# Etherent.net
KiCad netlist of a schematic drawn in Altium Designer
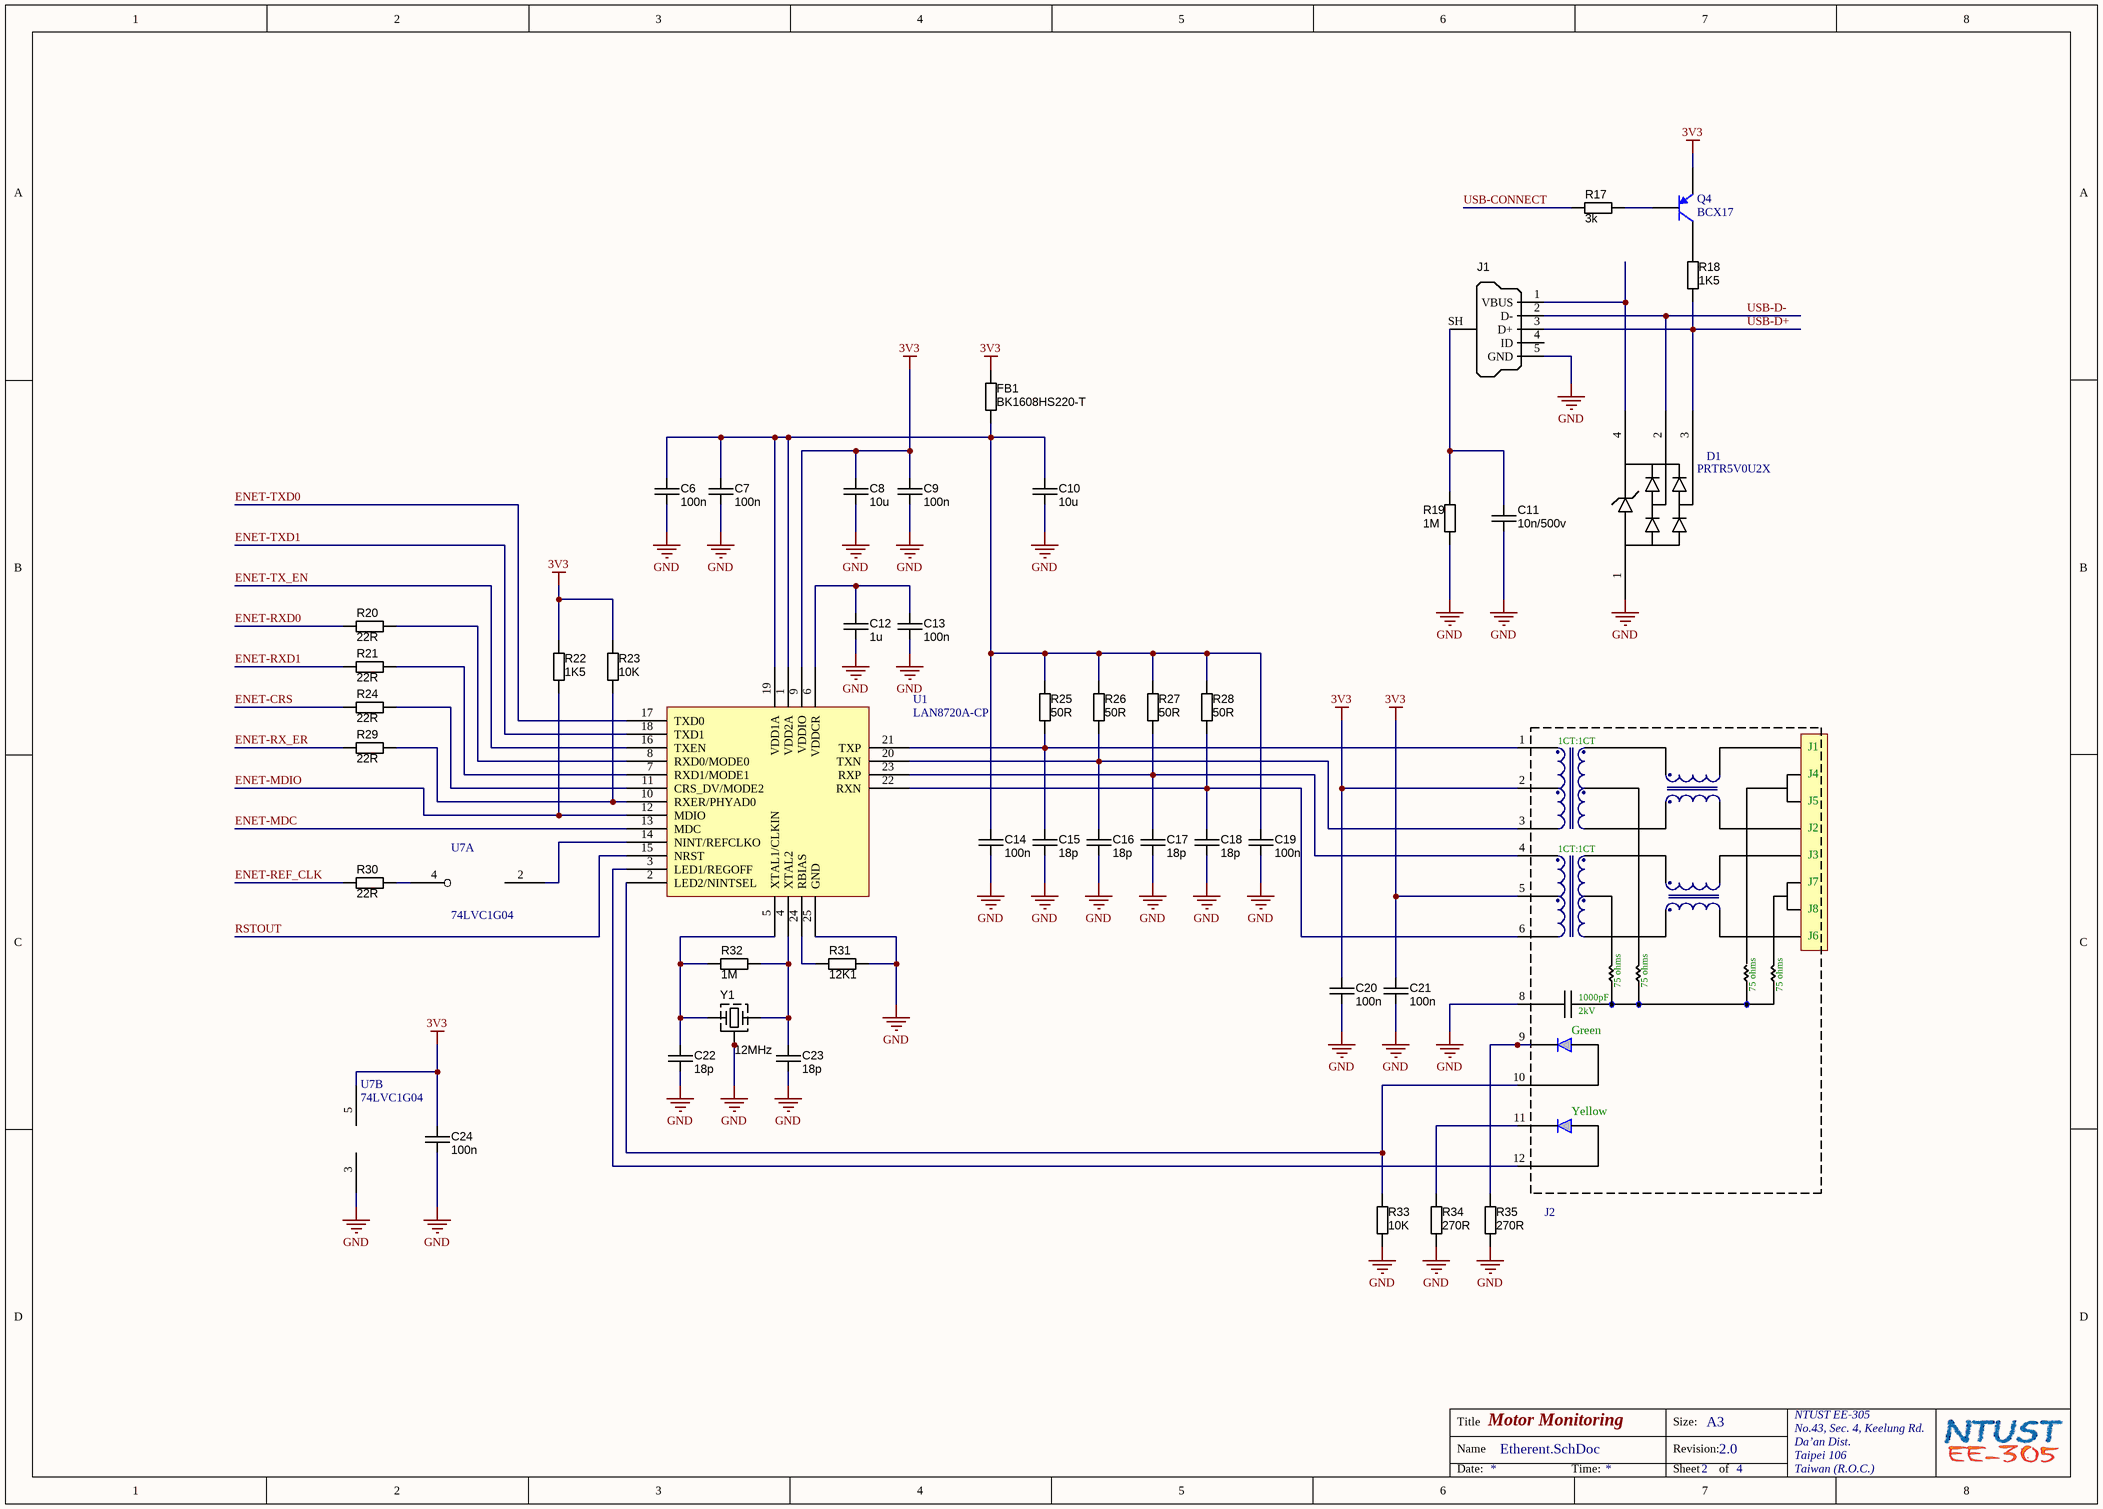
[diagram p0: Etherent.SchDoc]

(export (version "E")
  (design (tool "Eeschema 10.0.6"))
  (components
    (comp (ref "C6")
      (value "100n")
      (footprint "CAPC1608N")
      (description "Capacitor SMD Cer 100nF 10% 50V X7R 0805")
      (fields (field (name "TOLERANCE") "?0%") (field (name "Comment") "approved sub OK"))
      (libsource (lib "PBL - Capacitors") (part "CAPC_100n_0805"))
    )
    (comp (ref "C7")
      (value "100n")
      (footprint "CAPC1608N")
      (description "Capacitor SMD Cer 100nF 10% 50V X7R 0805")
      (fields (field (name "TOLERANCE") "?0%") (field (name "Comment") "approved sub OK"))
      (libsource (lib "PBL - Capacitors") (part "CAPC_100n_0805"))
    )
    (comp (ref "C8")
      (value "10u")
      (footprint "CAPC1608N")
      (description "Capacitor SMD Cer 100nF 10% 50V X7R 0805")
      (fields (field (name "TOLERANCE") "?0%") (field (name "Comment") "approved sub OK"))
      (libsource (lib "PBL - Capacitors") (part "CAPC_100n_0805"))
    )
    (comp (ref "C9")
      (value "100n")
      (footprint "CAPC1608N")
      (description "Capacitor SMD Cer 100nF 10% 50V X7R 0805")
      (fields (field (name "TOLERANCE") "?0%") (field (name "Comment") "approved sub OK"))
      (libsource (lib "PBL - Capacitors") (part "CAPC_100n_0805"))
    )
    (comp (ref "C10")
      (value "10u")
      (footprint "CAPC3216N")
      (description "Capacitor SMD Cer 100nF 10% 50V X7R 0805")
      (fields (field (name "TOLERANCE") "?0%") (field (name "Comment") "approved sub OK"))
      (libsource (lib "PBL - Capacitors") (part "CAPC_100n_0805"))
    )
    (comp (ref "C11")
      (value "10n/500v")
      (footprint "CAPC1608N")
      (description "Capacitor SMD Cer 100nF 10% 50V X7R 0805")
      (fields (field (name "TOLERANCE") "?0%") (field (name "Comment") "approved sub OK"))
      (libsource (lib "PBL - Capacitors") (part "CAPC_100n_0805"))
    )
    (comp (ref "C12")
      (value "1u")
      (footprint "CAPC2012N")
      (description "Capacitor SMD Cer 100nF 10% 50V X7R 0805")
      (fields (field (name "TOLERANCE") "?0%") (field (name "Comment") "approved sub OK"))
      (libsource (lib "PBL - Capacitors") (part "CAPC_100n_0805"))
    )
    (comp (ref "C13")
      (value "100n")
      (footprint "CAPC1608N")
      (description "Capacitor SMD Cer 100nF 10% 50V X7R 0805")
      (fields (field (name "TOLERANCE") "?0%") (field (name "Comment") "approved sub OK"))
      (libsource (lib "PBL - Capacitors") (part "CAPC_100n_0805"))
    )
    (comp (ref "C14")
      (value "100n")
      (footprint "CAPC1608N")
      (description "Capacitor SMD Cer 100nF 10% 50V X7R 0805")
      (fields (field (name "TOLERANCE") "?0%") (field (name "Comment") "approved sub OK"))
      (libsource (lib "PBL - Capacitors") (part "CAPC_100n_0805"))
    )
    (comp (ref "C15")
      (value "18p")
      (footprint "CAPC1005N")
      (description "Capacitor SMD Cer 100nF 10% 50V X7R 0805")
      (fields (field (name "TOLERANCE") "?0%") (field (name "Comment") "approved sub OK"))
      (libsource (lib "PBL - Capacitors") (part "CAPC_100n_0805"))
    )
    (comp (ref "C16")
      (value "18p")
      (footprint "CAPC1005N")
      (description "Capacitor SMD Cer 100nF 10% 50V X7R 0805")
      (fields (field (name "TOLERANCE") "?0%") (field (name "Comment") "approved sub OK"))
      (libsource (lib "PBL - Capacitors") (part "CAPC_100n_0805"))
    )
    (comp (ref "C17")
      (value "18p")
      (footprint "CAPC1005N")
      (description "Capacitor SMD Cer 100nF 10% 50V X7R 0805")
      (fields (field (name "TOLERANCE") "?0%") (field (name "Comment") "approved sub OK"))
      (libsource (lib "PBL - Capacitors") (part "CAPC_100n_0805"))
    )
    (comp (ref "C18")
      (value "18p")
      (footprint "CAPC1005N")
      (description "Capacitor SMD Cer 100nF 10% 50V X7R 0805")
      (fields (field (name "TOLERANCE") "?0%") (field (name "Comment") "approved sub OK"))
      (libsource (lib "PBL - Capacitors") (part "CAPC_100n_0805"))
    )
    (comp (ref "C19")
      (value "100n")
      (footprint "CAPC1608N")
      (description "Capacitor SMD Cer 100nF 10% 50V X7R 0805")
      (fields (field (name "TOLERANCE") "?0%") (field (name "Comment") "approved sub OK"))
      (libsource (lib "PBL - Capacitors") (part "CAPC_100n_0805"))
    )
    (comp (ref "C20")
      (value "100n")
      (footprint "CAPC1608N")
      (description "Capacitor SMD Cer 100nF 10% 50V X7R 0805")
      (fields (field (name "TOLERANCE") "?0%") (field (name "Comment") "approved sub OK"))
      (libsource (lib "PBL - Capacitors") (part "CAPC_100n_0805"))
    )
    (comp (ref "C21")
      (value "100n")
      (footprint "CAPC1608N")
      (description "Capacitor SMD Cer 100nF 10% 50V X7R 0805")
      (fields (field (name "TOLERANCE") "?0%") (field (name "Comment") "approved sub OK"))
      (libsource (lib "PBL - Capacitors") (part "CAPC_100n_0805"))
    )
    (comp (ref "C22")
      (value "18p")
      (footprint "CAPC1005N")
      (description "Capacitor SMD Cer 100nF 10% 50V X7R 0805")
      (fields (field (name "TOLERANCE") "?0%") (field (name "Comment") "approved sub OK"))
      (libsource (lib "PBL - Capacitors") (part "CAPC_100n_0805"))
    )
    (comp (ref "C23")
      (value "18p")
      (footprint "CAPC1005N")
      (description "Capacitor SMD Cer 100nF 10% 50V X7R 0805")
      (fields (field (name "TOLERANCE") "?0%") (field (name "Comment") "approved sub OK"))
      (libsource (lib "PBL - Capacitors") (part "CAPC_100n_0805"))
    )
    (comp (ref "C24")
      (value "100n")
      (footprint "CAPC1608N")
      (description "Capacitor SMD Cer 100nF 10% 50V X7R 0805")
      (fields (field (name "TOLERANCE") "?0%") (field (name "Comment") "approved sub OK"))
      (libsource (lib "PBL - Capacitors") (part "CAPC_100n_0805"))
    )
    (comp (ref "D1")
      (value "PRTR5V0U2X")
      (footprint "SOT190P230X120-4N")
      (libsource (lib "Schlib1") (part "PRTR5V0U2X"))
    )
    (comp (ref "FB1")
      (value "BK1608HS220-T")
      (footprint "CAPC3216N")
      (description "Resistor SMD chip 330 Ohm 0.063W 5% 0402")
      (fields (field (name "TOLERANCE") "?%") (field (name "Comment") "Thick Film"))
      (libsource (lib "") (part "RES_330R_0402_5%_1"))
    )
    (comp (ref "J1")
      (value "USB Micro Type B")
      (footprint "USB_Micro-B_FCI_SMD")
      (description "Connector SMD-THD USB Micro Type B middle mount")
      (libsource (lib "PBL - Connectors") (part "USB_Micro_TypeB_FCI"))
    )
    (comp (ref "J2")
      (value "~")
      (footprint "ARJC01-111002T")
      (description "10/100 Base-Tx Tap Up RJ45 with LED")
      (libsource (lib "Schlib1") (part "ARJC01-111002T"))
    )
    (comp (ref "Q4")
      (value "BCX17")
      (footprint "SOT23-3N")
      (description "PNP General Purpose Transistors")
      (fields (field (name "PUBLISHER") "Altium Limited"))
      (libsource (lib "Schlib1") (part "BCX17"))
    )
    (comp (ref "R17")
      (value "3k")
      (footprint "RESC1005N")
      (description "Resistor SMD chip 330 Ohm 0.063W 5% 0402")
      (fields (field (name "TOLERANCE") "?%") (field (name "Comment") "Thick Film"))
      (libsource (lib "") (part "RES_330R_0402_5%_2"))
    )
    (comp (ref "R18")
      (value "1K5")
      (footprint "RESC1005N")
      (description "Resistor SMD chip 330 Ohm 0.063W 5% 0402")
      (fields (field (name "TOLERANCE") "?%") (field (name "Comment") "Thick Film"))
      (libsource (lib "PBL - Resistors") (part "RES_330R_0402_5%"))
    )
    (comp (ref "R19")
      (value "1M")
      (footprint "RESC1005N")
      (description "Resistor SMD chip 330 Ohm 0.063W 5% 0402")
      (fields (field (name "TOLERANCE") "?%") (field (name "Comment") "Thick Film"))
      (libsource (lib "") (part "RES_330R_0402_5%_1"))
    )
    (comp (ref "R20")
      (value "22R")
      (footprint "RESC1005N")
      (description "Resistor SMD chip 330 Ohm 0.063W 5% 0402")
      (fields (field (name "TOLERANCE") "?%") (field (name "Comment") "Thick Film"))
      (libsource (lib "") (part "RES_330R_0402_5%_3"))
    )
    (comp (ref "R21")
      (value "22R")
      (footprint "RESC1005N")
      (description "Resistor SMD chip 330 Ohm 0.063W 5% 0402")
      (fields (field (name "TOLERANCE") "?%") (field (name "Comment") "Thick Film"))
      (libsource (lib "") (part "RES_330R_0402_5%_3"))
    )
    (comp (ref "R22")
      (value "1K5")
      (footprint "RESC1005N")
      (description "Resistor SMD chip 330 Ohm 0.063W 5% 0402")
      (fields (field (name "TOLERANCE") "?%") (field (name "Comment") "Thick Film"))
      (libsource (lib "PBL - Resistors") (part "RES_330R_0402_5%"))
    )
    (comp (ref "R23")
      (value "10K")
      (footprint "RESC1005N")
      (description "Resistor SMD chip 330 Ohm 0.063W 5% 0402")
      (fields (field (name "TOLERANCE") "?%") (field (name "Comment") "Thick Film"))
      (libsource (lib "PBL - Resistors") (part "RES_330R_0402_5%"))
    )
    (comp (ref "R24")
      (value "22R")
      (footprint "RESC1005N")
      (description "Resistor SMD chip 330 Ohm 0.063W 5% 0402")
      (fields (field (name "TOLERANCE") "?%") (field (name "Comment") "Thick Film"))
      (libsource (lib "") (part "RES_330R_0402_5%_3"))
    )
    (comp (ref "R25")
      (value "50R")
      (footprint "RESC1005N")
      (description "Resistor SMD chip 330 Ohm 0.063W 5% 0402")
      (fields (field (name "TOLERANCE") "?%") (field (name "Comment") "Thick Film"))
      (libsource (lib "PBL - Resistors") (part "RES_330R_0402_5%"))
    )
    (comp (ref "R26")
      (value "50R")
      (footprint "RESC1005N")
      (description "Resistor SMD chip 330 Ohm 0.063W 5% 0402")
      (fields (field (name "TOLERANCE") "?%") (field (name "Comment") "Thick Film"))
      (libsource (lib "PBL - Resistors") (part "RES_330R_0402_5%"))
    )
    (comp (ref "R27")
      (value "50R")
      (footprint "RESC1005N")
      (description "Resistor SMD chip 330 Ohm 0.063W 5% 0402")
      (fields (field (name "TOLERANCE") "?%") (field (name "Comment") "Thick Film"))
      (libsource (lib "PBL - Resistors") (part "RES_330R_0402_5%"))
    )
    (comp (ref "R28")
      (value "50R")
      (footprint "RESC1005N")
      (description "Resistor SMD chip 330 Ohm 0.063W 5% 0402")
      (fields (field (name "TOLERANCE") "?%") (field (name "Comment") "Thick Film"))
      (libsource (lib "PBL - Resistors") (part "RES_330R_0402_5%"))
    )
    (comp (ref "R29")
      (value "22R")
      (footprint "RESC1005N")
      (description "Resistor SMD chip 330 Ohm 0.063W 5% 0402")
      (fields (field (name "TOLERANCE") "?%") (field (name "Comment") "Thick Film"))
      (libsource (lib "") (part "RES_330R_0402_5%_2"))
    )
    (comp (ref "R30")
      (value "22R")
      (footprint "RESC1005N")
      (description "Resistor SMD chip 330 Ohm 0.063W 5% 0402")
      (fields (field (name "TOLERANCE") "?%") (field (name "Comment") "Thick Film"))
      (libsource (lib "") (part "RES_330R_0402_5%_3"))
    )
    (comp (ref "R31")
      (value "12K1")
      (footprint "RESC1005N")
      (description "Resistor SMD chip 330 Ohm 0.063W 5% 0402")
      (fields (field (name "TOLERANCE") "?%") (field (name "Comment") "Thick Film"))
      (libsource (lib "") (part "RES_330R_0402_5%_2"))
    )
    (comp (ref "R32")
      (value "1M")
      (footprint "RESC1005N")
      (description "Resistor SMD chip 330 Ohm 0.063W 5% 0402")
      (fields (field (name "TOLERANCE") "?%") (field (name "Comment") "Thick Film"))
      (libsource (lib "") (part "RES_330R_0402_5%_3"))
    )
    (comp (ref "R33")
      (value "10K")
      (footprint "RESC1005N")
      (description "Resistor SMD chip 330 Ohm 0.063W 5% 0402")
      (fields (field (name "TOLERANCE") "?%") (field (name "Comment") "Thick Film"))
      (libsource (lib "PBL - Resistors") (part "RES_330R_0402_5%"))
    )
    (comp (ref "R34")
      (value "270R")
      (footprint "RESC1005N")
      (description "Resistor SMD chip 330 Ohm 0.063W 5% 0402")
      (fields (field (name "TOLERANCE") "?%") (field (name "Comment") "Thick Film"))
      (libsource (lib "") (part "RES_330R_0402_5%_1"))
    )
    (comp (ref "R35")
      (value "270R")
      (footprint "RESC1005N")
      (description "Resistor SMD chip 330 Ohm 0.063W 5% 0402")
      (fields (field (name "TOLERANCE") "?%") (field (name "Comment") "Thick Film"))
      (libsource (lib "") (part "RES_330R_0402_5%_1"))
    )
    (comp (ref "U1")
      (value "LAN8720A-CP")
      (footprint "QFN-MJ24")
      (libsource (lib "Schlib1") (part "LAN8720A-CP"))
    )
    (comp (ref "U7")
      (value "74LVC1G04")
      (footprint "SOT-23-CT5_N")
      (libsource (lib "Schlib1") (part "74LVC1G04"))
    )
    (comp (ref "Y1")
      (value "12MHz")
      (footprint "CRYSTAL_4-LCC")
      (description "Oscillator Crystal 27.12 MHz 10ppm")
      (libsource (lib "PBL - Resonators") (part "CRYSTAL_27M12"))
    )
  )
  (nets
    (net (code "1") (name "/ENET-CRS") (class "Default")
      (node (ref "R24") (pin "1") (pinfunction "1_1") (pintype "passive"))
    )
    (net (code "2") (name "/ENET-MDC") (class "Default")
      (node (ref "U1") (pin "13") (pinfunction "MDC_13") (pintype "passive"))
    )
    (net (code "3") (name "/ENET-MDIO") (class "Default")
      (node (ref "R22") (pin "2") (pinfunction "2_2") (pintype "passive"))
      (node (ref "U1") (pin "12") (pinfunction "MDIO_12") (pintype "passive"))
    )
    (net (code "4") (name "/ENET-REF_CLK") (class "Default")
      (node (ref "R30") (pin "1") (pinfunction "1_1") (pintype "passive"))
    )
    (net (code "5") (name "/ENET-RXD0") (class "Default")
      (node (ref "R20") (pin "1") (pinfunction "1_1") (pintype "passive"))
    )
    (net (code "6") (name "/ENET-RXD1") (class "Default")
      (node (ref "R21") (pin "1") (pinfunction "1_1") (pintype "passive"))
    )
    (net (code "7") (name "/ENET-RX_ER") (class "Default")
      (node (ref "R29") (pin "2") (pinfunction "2_2") (pintype "passive"))
    )
    (net (code "8") (name "/ENET-TXD0") (class "Default")
      (node (ref "U1") (pin "17") (pinfunction "TXD0_17") (pintype "passive"))
    )
    (net (code "9") (name "/ENET-TXD1") (class "Default")
      (node (ref "U1") (pin "18") (pinfunction "TXD1_18") (pintype "passive"))
    )
    (net (code "10") (name "/ENET-TX_EN") (class "Default")
      (node (ref "U1") (pin "16") (pinfunction "TXEN_16") (pintype "passive"))
    )
    (net (code "11") (name "/RSTOUT") (class "Default")
      (node (ref "U1") (pin "15") (pinfunction "NRST_15") (pintype "passive"))
    )
    (net (code "12") (name "/USB-CONNECT") (class "Default")
      (node (ref "R17") (pin "2") (pinfunction "2_2") (pintype "passive"))
    )
    (net (code "13") (name "/USB-D+") (class "Default")
      (node (ref "D1") (pin "3") (pinfunction "I/O_2_3") (pintype "passive"))
      (node (ref "J1") (pin "3") (pinfunction "D+_3") (pintype "passive"))
      (node (ref "R18") (pin "2") (pinfunction "2_2") (pintype "passive"))
    )
    (net (code "14") (name "/USB-D-") (class "Default")
      (node (ref "D1") (pin "2") (pinfunction "I/O_1_2") (pintype "passive"))
      (node (ref "J1") (pin "2") (pinfunction "D-_2") (pintype "passive"))
    )
    (net (code "15") (name "3V3") (class "Default")
      (node (ref "C20") (pin "1") (pintype "passive"))
      (node (ref "C21") (pin "1") (pintype "passive"))
      (node (ref "C24") (pin "1") (pintype "passive"))
      (node (ref "C8") (pin "1") (pintype "passive"))
      (node (ref "C9") (pin "1") (pintype "passive"))
      (node (ref "FB1") (pin "2") (pinfunction "2_2") (pintype "passive"))
      (node (ref "J2") (pin "2") (pinfunction "CTD_2") (pintype "passive"))
      (node (ref "J2") (pin "5") (pinfunction "CRD_5") (pintype "passive"))
      (node (ref "Q4") (pin "2") (pinfunction "E_2") (pintype "passive"))
      (node (ref "R22") (pin "1") (pinfunction "1_1") (pintype "passive"))
      (node (ref "R23") (pin "1") (pinfunction "1_1") (pintype "passive"))
      (node (ref "U1") (pin "9") (pinfunction "VDDIO_9") (pintype "passive"))
      (node (ref "U7") (pin "5") (pinfunction "VCC_5") (pintype "passive"))
    )
    (net (code "16") (name "GND") (class "Default")
      (node (ref "C10") (pin "2") (pintype "passive"))
      (node (ref "C11") (pin "2") (pintype "passive"))
      (node (ref "C12") (pin "2") (pintype "passive"))
      (node (ref "C13") (pin "2") (pintype "passive"))
      (node (ref "C14") (pin "1") (pintype "passive"))
      (node (ref "C15") (pin "1") (pintype "passive"))
      (node (ref "C16") (pin "1") (pintype "passive"))
      (node (ref "C17") (pin "1") (pintype "passive"))
      (node (ref "C18") (pin "1") (pintype "passive"))
      (node (ref "C19") (pin "1") (pintype "passive"))
      (node (ref "C20") (pin "2") (pintype "passive"))
      (node (ref "C21") (pin "2") (pintype "passive"))
      (node (ref "C22") (pin "1") (pintype "passive"))
      (node (ref "C23") (pin "1") (pintype "passive"))
      (node (ref "C24") (pin "2") (pintype "passive"))
      (node (ref "C6") (pin "2") (pintype "passive"))
      (node (ref "C7") (pin "2") (pintype "passive"))
      (node (ref "C8") (pin "2") (pintype "passive"))
      (node (ref "C9") (pin "2") (pintype "passive"))
      (node (ref "D1") (pin "1") (pinfunction "GND_1") (pintype "passive"))
      (node (ref "J1") (pin "5") (pinfunction "GND_5") (pintype "passive"))
      (node (ref "J2") (pin "8") (pinfunction "Shield_8") (pintype "passive"))
      (node (ref "R19") (pin "1") (pinfunction "1_1") (pintype "passive"))
      (node (ref "R31") (pin "1") (pinfunction "1_1") (pintype "passive"))
      (node (ref "R33") (pin "2") (pinfunction "2_2") (pintype "passive"))
      (node (ref "R34") (pin "1") (pinfunction "1_1") (pintype "passive"))
      (node (ref "R35") (pin "1") (pinfunction "1_1") (pintype "passive"))
      (node (ref "U1") (pin "25") (pinfunction "GND_25") (pintype "passive"))
      (node (ref "U7") (pin "3") (pinfunction "GND_3") (pintype "passive"))
      (node (ref "Y1") (pin "2") (pinfunction "GND_2") (pintype "passive"))
      (node (ref "Y1") (pin "4") (pinfunction "GND_4") (pintype "passive"))
    )
    (net (code "17") (name "Net-(D1-VCC)") (class "Default")
      (node (ref "D1") (pin "4") (pinfunction "VCC_4") (pintype "passive"))
      (node (ref "J1") (pin "1") (pinfunction "VBUS_1") (pintype "passive"))
    )
    (net (code "18") (name "Net-(J1-Shell)") (class "Default")
      (node (ref "C11") (pin "1") (pintype "passive"))
      (node (ref "J1") (pin "SH") (pinfunction "Shell_SH") (pintype "passive"))
      (node (ref "R19") (pin "2") (pinfunction "2_2") (pintype "passive"))
    )
    (net (code "19") (name "Net-(J2-Pad9)") (class "Default")
      (node (ref "J2") (pin "9") (pinfunction "9_9") (pintype "passive"))
      (node (ref "R35") (pin "2") (pinfunction "2_2") (pintype "passive"))
    )
    (net (code "20") (name "Net-(J2-Pad11)") (class "Default")
      (node (ref "J2") (pin "11") (pinfunction "11_11") (pintype "passive"))
      (node (ref "R34") (pin "2") (pinfunction "2_2") (pintype "passive"))
    )
    (net (code "21") (name "Net-(J2-RD+)") (class "Default")
      (node (ref "C17") (pin "2") (pintype "passive"))
      (node (ref "J2") (pin "4") (pinfunction "RD+_4") (pintype "passive"))
      (node (ref "R27") (pin "2") (pinfunction "2_2") (pintype "passive"))
      (node (ref "U1") (pin "23") (pinfunction "RXP_23") (pintype "passive"))
    )
    (net (code "22") (name "Net-(J2-RD-)") (class "Default")
      (node (ref "C18") (pin "2") (pintype "passive"))
      (node (ref "J2") (pin "6") (pinfunction "RD-_6") (pintype "passive"))
      (node (ref "R28") (pin "2") (pinfunction "2_2") (pintype "passive"))
      (node (ref "U1") (pin "22") (pinfunction "RXN_22") (pintype "passive"))
    )
    (net (code "23") (name "Net-(J2-TD+)") (class "Default")
      (node (ref "C15") (pin "2") (pintype "passive"))
      (node (ref "J2") (pin "1") (pinfunction "TD+_1") (pintype "passive"))
      (node (ref "R25") (pin "2") (pinfunction "2_2") (pintype "passive"))
      (node (ref "U1") (pin "21") (pinfunction "TXP_21") (pintype "passive"))
    )
    (net (code "24") (name "Net-(J2-TD-)") (class "Default")
      (node (ref "C16") (pin "2") (pintype "passive"))
      (node (ref "J2") (pin "3") (pinfunction "TD-_3") (pintype "passive"))
      (node (ref "R26") (pin "2") (pinfunction "2_2") (pintype "passive"))
      (node (ref "U1") (pin "20") (pinfunction "TXN_20") (pintype "passive"))
    )
    (net (code "25") (name "Net-(Q4-B)") (class "Default")
      (node (ref "Q4") (pin "1") (pinfunction "B_1") (pintype "passive"))
      (node (ref "R17") (pin "1") (pinfunction "1_1") (pintype "passive"))
    )
    (net (code "26") (name "Net-(Q4-C)") (class "Default")
      (node (ref "Q4") (pin "3") (pinfunction "C_3") (pintype "passive"))
      (node (ref "R18") (pin "1") (pinfunction "1_1") (pintype "passive"))
    )
    (net (code "27") (name "Net-(R30-Pad2)") (class "Default")
      (node (ref "R30") (pin "2") (pinfunction "2_2") (pintype "passive"))
      (node (ref "U7") (pin "4") (pintype "passive"))
    )
    (net (code "28") (name "Net-(U1-CRS_DV{slash}MODE2)") (class "Default")
      (node (ref "R24") (pin "2") (pinfunction "2_2") (pintype "passive"))
      (node (ref "U1") (pin "11") (pinfunction "CRS_DV/MODE2_11") (pintype "passive"))
    )
    (net (code "29") (name "Net-(U1-LED1{slash}REGOFF)") (class "Default")
      (node (ref "J2") (pin "12") (pinfunction "12_12") (pintype "passive"))
      (node (ref "U1") (pin "3") (pinfunction "LED1/REGOFF_3") (pintype "passive"))
    )
    (net (code "30") (name "Net-(U1-LED2{slash}NINTSEL)") (class "Default")
      (node (ref "J2") (pin "10") (pinfunction "10_10") (pintype "passive"))
      (node (ref "R33") (pin "1") (pinfunction "1_1") (pintype "passive"))
      (node (ref "U1") (pin "2") (pinfunction "LED2/NINTSEL_2") (pintype "passive"))
    )
    (net (code "31") (name "Net-(U1-NINT{slash}REFCLKO)") (class "Default")
      (node (ref "U1") (pin "14") (pinfunction "NINT/REFCLKO_14") (pintype "passive"))
      (node (ref "U7") (pin "2") (pintype "passive"))
    )
    (net (code "32") (name "Net-(U1-RBIAS)") (class "Default")
      (node (ref "R31") (pin "2") (pinfunction "2_2") (pintype "passive"))
      (node (ref "U1") (pin "24") (pinfunction "RBIAS_24") (pintype "passive"))
    )
    (net (code "33") (name "Net-(U1-RXD0{slash}MODE0)") (class "Default")
      (node (ref "R20") (pin "2") (pinfunction "2_2") (pintype "passive"))
      (node (ref "U1") (pin "8") (pinfunction "RXD0/MODE0_8") (pintype "passive"))
    )
    (net (code "34") (name "Net-(U1-RXD1{slash}MODE1)") (class "Default")
      (node (ref "R21") (pin "2") (pinfunction "2_2") (pintype "passive"))
      (node (ref "U1") (pin "7") (pinfunction "RXD1/MODE1_7") (pintype "passive"))
    )
    (net (code "35") (name "Net-(U1-RXER{slash}PHYAD0)") (class "Default")
      (node (ref "R23") (pin "2") (pinfunction "2_2") (pintype "passive"))
      (node (ref "R29") (pin "1") (pinfunction "1_1") (pintype "passive"))
      (node (ref "U1") (pin "10") (pinfunction "RXER/PHYAD0_10") (pintype "passive"))
    )
    (net (code "36") (name "Net-(U1-VDD1A)") (class "Default")
      (node (ref "C10") (pin "1") (pintype "passive"))
      (node (ref "C14") (pin "2") (pintype "passive"))
      (node (ref "C19") (pin "2") (pintype "passive"))
      (node (ref "C6") (pin "1") (pintype "passive"))
      (node (ref "C7") (pin "1") (pintype "passive"))
      (node (ref "FB1") (pin "1") (pinfunction "1_1") (pintype "passive"))
      (node (ref "R25") (pin "1") (pinfunction "1_1") (pintype "passive"))
      (node (ref "R26") (pin "1") (pinfunction "1_1") (pintype "passive"))
      (node (ref "R27") (pin "1") (pinfunction "1_1") (pintype "passive"))
      (node (ref "R28") (pin "1") (pinfunction "1_1") (pintype "passive"))
      (node (ref "U1") (pin "1") (pinfunction "VDD2A_1") (pintype "passive"))
      (node (ref "U1") (pin "19") (pinfunction "VDD1A_19") (pintype "passive"))
    )
    (net (code "37") (name "Net-(U1-VDDCR)") (class "Default")
      (node (ref "C12") (pin "1") (pintype "passive"))
      (node (ref "C13") (pin "1") (pintype "passive"))
      (node (ref "U1") (pin "6") (pinfunction "VDDCR_6") (pintype "passive"))
    )
    (net (code "38") (name "Net-(U1-XTAL1{slash}CLKIN)") (class "Default")
      (node (ref "C22") (pin "2") (pintype "passive"))
      (node (ref "R32") (pin "1") (pinfunction "1_1") (pintype "passive"))
      (node (ref "U1") (pin "5") (pinfunction "XTAL1/CLKIN_5") (pintype "passive"))
      (node (ref "Y1") (pin "1") (pinfunction "X_1") (pintype "passive"))
    )
    (net (code "39") (name "Net-(U1-XTAL2)") (class "Default")
      (node (ref "C23") (pin "2") (pintype "passive"))
      (node (ref "R32") (pin "2") (pinfunction "2_2") (pintype "passive"))
      (node (ref "U1") (pin "4") (pinfunction "XTAL2_4") (pintype "passive"))
      (node (ref "Y1") (pin "3") (pinfunction "X_3") (pintype "passive"))
    )
    (net (code "40") (name "unconnected-(J1-ID-Pad4)") (class "Default")
      (node (ref "J1") (pin "4") (pinfunction "ID_4") (pintype "passive"))
    )
  )
)
